# Mainboard.net
KiCad netlist of a schematic drawn in Altium Designer
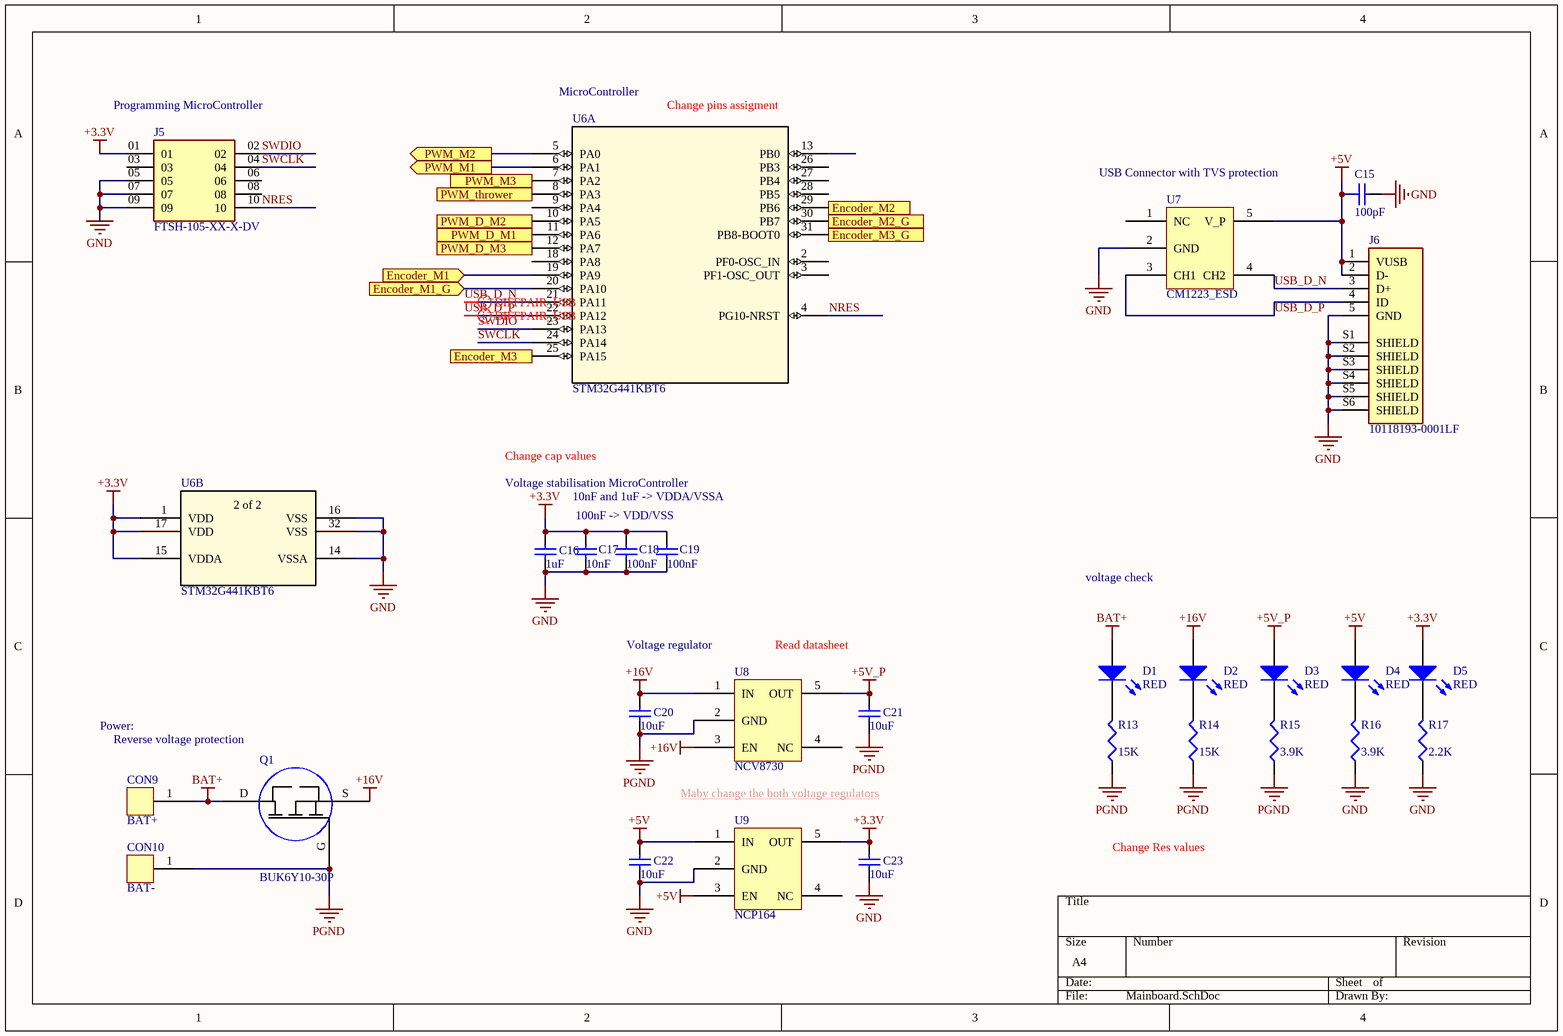
[diagram p0: Mainboard.SchDoc]

(export (version "E")
  (design (tool "Eeschema 10.0.6"))
  (components
    (comp (ref "C15")
      (value "100pF")
      (footprint "1608[0603]")
      (description "Capacitor (Semiconductor SIM Model)")
      (fields (field (name "Comment") "Cap Semi") (field (name "PUBLISHER") "Altium Limited"))
      (libsource (lib "Miscellaneous Devices") (part "Cap Semi"))
    )
    (comp (ref "C16")
      (value "1uF")
      (footprint "1608[0603]")
      (description "Capacitor (Semiconductor SIM Model)")
      (fields (field (name "Comment") "Cap Semi") (field (name "PUBLISHER") "Altium Limited"))
      (libsource (lib "Miscellaneous Devices") (part "Cap Semi"))
    )
    (comp (ref "C17")
      (value "10nF")
      (footprint "1608[0603]")
      (description "Capacitor (Semiconductor SIM Model)")
      (fields (field (name "Comment") "Cap Semi") (field (name "PUBLISHER") "Altium Limited"))
      (libsource (lib "Miscellaneous Devices") (part "Cap Semi"))
    )
    (comp (ref "C18")
      (value "100nF")
      (footprint "1608[0603]")
      (description "Capacitor (Semiconductor SIM Model)")
      (fields (field (name "Comment") "Cap Semi") (field (name "PUBLISHER") "Altium Limited"))
      (libsource (lib "Miscellaneous Devices") (part "Cap Semi"))
    )
    (comp (ref "C19")
      (value "100nF")
      (footprint "1608[0603]")
      (description "Capacitor (Semiconductor SIM Model)")
      (fields (field (name "Comment") "Cap Semi") (field (name "PUBLISHER") "Altium Limited"))
      (libsource (lib "Miscellaneous Devices") (part "Cap Semi"))
    )
    (comp (ref "C20")
      (value "10uF")
      (footprint "C1210")
      (description "Capacitor (Semiconductor SIM Model)")
      (fields (field (name "Comment") "Cap Semi") (field (name "PUBLISHER") "Altium Limited"))
      (libsource (lib "Miscellaneous Devices") (part "Cap Semi"))
    )
    (comp (ref "C21")
      (value "10uF")
      (footprint "C1210")
      (description "Capacitor (Semiconductor SIM Model)")
      (fields (field (name "Comment") "Cap Semi") (field (name "PUBLISHER") "Altium Limited"))
      (libsource (lib "Miscellaneous Devices") (part "Cap Semi"))
    )
    (comp (ref "C22")
      (value "10uF")
      (footprint "C1210")
      (description "Capacitor (Semiconductor SIM Model)")
      (fields (field (name "Comment") "Cap Semi") (field (name "PUBLISHER") "Altium Limited"))
      (libsource (lib "Miscellaneous Devices") (part "Cap Semi"))
    )
    (comp (ref "C23")
      (value "10uF")
      (footprint "C1210")
      (description "Capacitor (Semiconductor SIM Model)")
      (fields (field (name "Comment") "Cap Semi") (field (name "PUBLISHER") "Altium Limited"))
      (libsource (lib "Miscellaneous Devices") (part "Cap Semi"))
    )
    (comp (ref "CON9")
      (value "BAT+")
      (footprint "con_soldering")
      (libsource (lib "con_soldering") (part "Con_soldering"))
    )
    (comp (ref "CON10")
      (value "BAT-")
      (footprint "con_soldering")
      (libsource (lib "con_soldering") (part "Con_soldering"))
    )
    (comp (ref "D1")
      (value "RED")
      (footprint "3.2X1.6X1.1")
      (description "Typical RED, GREEN, YELLOW, AMBER GaAs LED")
      (fields (field (name "PUBLISHER") "Altium Limited"))
      (libsource (lib "Miscellaneous Devices") (part "LED2"))
    )
    (comp (ref "D2")
      (value "RED")
      (footprint "3.2X1.6X1.1")
      (description "Typical RED, GREEN, YELLOW, AMBER GaAs LED")
      (fields (field (name "PUBLISHER") "Altium Limited"))
      (libsource (lib "Miscellaneous Devices") (part "LED2"))
    )
    (comp (ref "D3")
      (value "RED")
      (footprint "3.2X1.6X1.1")
      (description "Typical RED, GREEN, YELLOW, AMBER GaAs LED")
      (fields (field (name "PUBLISHER") "Altium Limited"))
      (libsource (lib "Miscellaneous Devices") (part "LED2"))
    )
    (comp (ref "D4")
      (value "RED")
      (footprint "3.2X1.6X1.1")
      (description "Typical RED, GREEN, YELLOW, AMBER GaAs LED")
      (fields (field (name "PUBLISHER") "Altium Limited"))
      (libsource (lib "Miscellaneous Devices") (part "LED2"))
    )
    (comp (ref "D5")
      (value "RED")
      (footprint "3.2X1.6X1.1")
      (description "Typical RED, GREEN, YELLOW, AMBER GaAs LED")
      (fields (field (name "PUBLISHER") "Altium Limited"))
      (libsource (lib "Miscellaneous Devices") (part "LED2"))
    )
    (comp (ref "J5")
      (value "FTSH-105-XX-X-DV")
      (footprint "SAMTEC_FTSH-105-XX-X-DV:SAMTEC_FTSH-105-XX-X-DV")
      (description "Connector Header Surface Mount 10 position 0.050\" (1.27mm)")
      (libsource (lib "FTSH-105-XX-X-DV") (part "FTSH-105-XX-X-DV"))
    )
    (comp (ref "J6")
      (value "10118193-0001LF")
      (footprint "FCI_10118193-0001LF")
      (description "USB - micro B USB 2.0 Receptacle Connector 5 Position Surface Mount, Right Angle; Through Hole")
      (fields (field (name "MF") "Amphenol ICC"))
      (libsource (lib "SnapEDAsch") (part "10118193-0001LF"))
    )
    (comp (ref "Q1")
      (value "BUK6Y10-30P")
      (footprint "TRANS_PSMN5R5-60YS,115")
      (libsource (lib "BUK6Y10-30P") (part "BUK6Y10-30P"))
    )
    (comp (ref "R13")
      (value "15K")
      (footprint "J1-0603")
      (description "Resistor")
      (fields (field (name "Comment") "Res3") (field (name "PUBLISHER") "Altium Limited"))
      (libsource (lib "Miscellaneous Devices") (part "Res3"))
    )
    (comp (ref "R14")
      (value "15K")
      (footprint "J1-0603")
      (description "Resistor")
      (fields (field (name "Comment") "Res3") (field (name "PUBLISHER") "Altium Limited"))
      (libsource (lib "Miscellaneous Devices") (part "Res3"))
    )
    (comp (ref "R15")
      (value "3.9K")
      (footprint "J1-0603")
      (description "Resistor")
      (fields (field (name "Comment") "Res3") (field (name "PUBLISHER") "Altium Limited"))
      (libsource (lib "Miscellaneous Devices") (part "Res3"))
    )
    (comp (ref "R16")
      (value "3.9K")
      (footprint "J1-0603")
      (description "Resistor")
      (fields (field (name "Comment") "Res3") (field (name "PUBLISHER") "Altium Limited"))
      (libsource (lib "Miscellaneous Devices") (part "Res3"))
    )
    (comp (ref "R17")
      (value "2.2K")
      (footprint "J1-0603")
      (description "Resistor")
      (fields (field (name "Comment") "Res3") (field (name "PUBLISHER") "Altium Limited"))
      (libsource (lib "Miscellaneous Devices") (part "Res3"))
    )
    (comp (ref "U6")
      (value "STM32G441KBT6")
      (footprint "LQFP-32")
      (description "No Description Available")
      (fields (field (name "COPYRIGHT") "Copyright (C) 2021 Ultra Librarian. All rights reserved."))
      (libsource (lib "STM32G441KBT6") (part "STM32G441KBT6"))
    )
    (comp (ref "U7")
      (value "CM1223_ESD")
      (footprint "CM1223_ESD")
      (libsource (lib "CM1223_ESD") (part "CM1223_ESD"))
    )
    (comp (ref "U8")
      (value "NCV8730")
      (footprint "NCP164CSN330T1G_Voltage_regulator")
      (libsource (lib "NCV8730") (part "NCV8730"))
    )
    (comp (ref "U9")
      (value "NCP164")
      (footprint "NCP164CSN330T1G_Voltage_regulator")
      (libsource (lib "NCP164_voltage_5to3V3") (part "NCP164"))
    )
  )
  (nets
    (net (code "1") (name "+3.3V") (class "Default")
      (node (ref "C16") (pin "2") (pinfunction "2_2") (pintype "passive"))
      (node (ref "C17") (pin "2") (pinfunction "2_2") (pintype "passive"))
      (node (ref "C18") (pin "2") (pinfunction "2_2") (pintype "passive"))
      (node (ref "C19") (pin "2") (pinfunction "2_2") (pintype "passive"))
      (node (ref "C23") (pin "2") (pinfunction "2_2") (pintype "passive"))
      (node (ref "D5") (pin "1") (pinfunction "A_1") (pintype "passive"))
      (node (ref "J5") (pin "01") (pinfunction "01_01") (pintype "passive"))
      (node (ref "U6") (pin "1") (pinfunction "VDD_1") (pintype "power_in"))
      (node (ref "U6") (pin "15") (pinfunction "VDDA_15") (pintype "power_in"))
      (node (ref "U6") (pin "17") (pinfunction "VDD_17") (pintype "power_in"))
      (node (ref "U9") (pin "5") (pinfunction "OUT_5") (pintype "passive"))
    )
    (net (code "2") (name "+5V") (class "Default")
      (node (ref "C15") (pin "2") (pinfunction "2_2") (pintype "passive"))
      (node (ref "C22") (pin "2") (pinfunction "2_2") (pintype "passive"))
      (node (ref "D4") (pin "1") (pinfunction "A_1") (pintype "passive"))
      (node (ref "J6") (pin "1") (pinfunction "VUSB_1") (pintype "passive"))
      (node (ref "J6") (pin "2") (pinfunction "D-_2") (pintype "passive"))
      (node (ref "U7") (pin "5") (pinfunction "V_P_5") (pintype "passive"))
      (node (ref "U9") (pin "1") (pinfunction "IN_1") (pintype "passive"))
      (node (ref "U9") (pin "3") (pinfunction "EN_3") (pintype "passive"))
    )
    (net (code "3") (name "+5V_P") (class "Default")
      (node (ref "C21") (pin "2") (pinfunction "2_2") (pintype "passive"))
      (node (ref "D3") (pin "1") (pinfunction "A_1") (pintype "passive"))
      (node (ref "U8") (pin "5") (pinfunction "OUT_5") (pintype "passive"))
    )
    (net (code "4") (name "+16V") (class "Default")
      (node (ref "C20") (pin "2") (pinfunction "2_2") (pintype "passive"))
      (node (ref "D2") (pin "1") (pinfunction "A_1") (pintype "passive"))
      (node (ref "Q1") (pin "S") (pinfunction "S_S") (pintype "passive"))
      (node (ref "U8") (pin "1") (pinfunction "IN_1") (pintype "passive"))
      (node (ref "U8") (pin "3") (pinfunction "EN_3") (pintype "passive"))
    )
    (net (code "5") (name "/Encoder_M1") (class "Default")
      (node (ref "U6") (pin "19") (pinfunction "PA9_19") (pintype "bidirectional"))
    )
    (net (code "6") (name "/Encoder_M1_G") (class "Default")
      (node (ref "U6") (pin "20") (pinfunction "PA10_20") (pintype "bidirectional"))
    )
    (net (code "7") (name "/Encoder_M2") (class "Default")
      (node (ref "U6") (pin "29") (pinfunction "PB6_29") (pintype "bidirectional"))
    )
    (net (code "8") (name "/Encoder_M2_G") (class "Default")
      (node (ref "U6") (pin "30") (pinfunction "PB7_30") (pintype "bidirectional"))
    )
    (net (code "9") (name "/Encoder_M3") (class "Default")
      (node (ref "U6") (pin "25") (pinfunction "PA15_25") (pintype "bidirectional"))
    )
    (net (code "10") (name "/Encoder_M3_G") (class "Default")
      (node (ref "U6") (pin "31") (pinfunction "PB8-BOOT0_31") (pintype "bidirectional"))
    )
    (net (code "11") (name "/NRES") (class "Default")
      (node (ref "J5") (pin "10") (pinfunction "10_10") (pintype "passive"))
      (node (ref "U6") (pin "4") (pinfunction "PG10-NRST_4") (pintype "bidirectional"))
    )
    (net (code "12") (name "/PWM_D_M1") (class "Default")
      (node (ref "U6") (pin "11") (pinfunction "PA6_11") (pintype "bidirectional"))
    )
    (net (code "13") (name "/PWM_D_M2") (class "Default")
      (node (ref "U6") (pin "10") (pinfunction "PA5_10") (pintype "bidirectional"))
    )
    (net (code "14") (name "/PWM_D_M3") (class "Default")
      (node (ref "U6") (pin "12") (pinfunction "PA7_12") (pintype "bidirectional"))
    )
    (net (code "15") (name "/PWM_M1") (class "Default")
      (node (ref "U6") (pin "6") (pinfunction "PA1_6") (pintype "bidirectional"))
    )
    (net (code "16") (name "/PWM_M2") (class "Default")
      (node (ref "U6") (pin "5") (pinfunction "PA0_5") (pintype "bidirectional"))
    )
    (net (code "17") (name "/PWM_M3") (class "Default")
      (node (ref "U6") (pin "7") (pinfunction "PA2_7") (pintype "bidirectional"))
    )
    (net (code "18") (name "/PWM_thrower") (class "Default")
      (node (ref "U6") (pin "8") (pinfunction "PA3_8") (pintype "bidirectional"))
    )
    (net (code "19") (name "/SWCLK") (class "Default")
      (node (ref "J5") (pin "04") (pinfunction "04_04") (pintype "passive"))
      (node (ref "U6") (pin "24") (pinfunction "PA14_24") (pintype "bidirectional"))
    )
    (net (code "20") (name "/SWDIO") (class "Default")
      (node (ref "J5") (pin "02") (pinfunction "02_02") (pintype "passive"))
      (node (ref "U6") (pin "23") (pinfunction "PA13_23") (pintype "bidirectional"))
    )
    (net (code "21") (name "/USB_D_N") (class "Default")
      (node (ref "J6") (pin "3") (pinfunction "D+_3") (pintype "passive"))
      (node (ref "U6") (pin "21") (pinfunction "PA11_21") (pintype "bidirectional"))
      (node (ref "U7") (pin "4") (pinfunction "CH2_4") (pintype "passive"))
    )
    (net (code "22") (name "/USB_D_P") (class "Default")
      (node (ref "J6") (pin "4") (pinfunction "ID_4") (pintype "passive"))
      (node (ref "U6") (pin "22") (pinfunction "PA12_22") (pintype "bidirectional"))
      (node (ref "U7") (pin "3") (pinfunction "CH1_3") (pintype "passive"))
    )
    (net (code "23") (name "BAT+") (class "Default")
      (node (ref "CON9") (pin "1") (pintype "passive"))
      (node (ref "D1") (pin "1") (pinfunction "A_1") (pintype "passive"))
      (node (ref "Q1") (pin "D") (pinfunction "D_D") (pintype "passive"))
    )
    (net (code "24") (name "GND") (class "Default")
      (node (ref "C15") (pin "1") (pinfunction "1_1") (pintype "passive"))
      (node (ref "C16") (pin "1") (pinfunction "1_1") (pintype "passive"))
      (node (ref "C17") (pin "1") (pinfunction "1_1") (pintype "passive"))
      (node (ref "C18") (pin "1") (pinfunction "1_1") (pintype "passive"))
      (node (ref "C19") (pin "1") (pinfunction "1_1") (pintype "passive"))
      (node (ref "C22") (pin "1") (pinfunction "1_1") (pintype "passive"))
      (node (ref "C23") (pin "1") (pinfunction "1_1") (pintype "passive"))
      (node (ref "J5") (pin "05") (pinfunction "05_05") (pintype "passive"))
      (node (ref "J5") (pin "07") (pinfunction "07_07") (pintype "passive"))
      (node (ref "J5") (pin "09") (pinfunction "09_09") (pintype "passive"))
      (node (ref "J6") (pin "5") (pinfunction "GND_5") (pintype "passive"))
      (node (ref "J6") (pin "S1") (pinfunction "SHIELD_S1") (pintype "passive"))
      (node (ref "J6") (pin "S2") (pinfunction "SHIELD_S2") (pintype "passive"))
      (node (ref "J6") (pin "S3") (pinfunction "SHIELD_S3") (pintype "passive"))
      (node (ref "J6") (pin "S4") (pinfunction "SHIELD_S4") (pintype "passive"))
      (node (ref "J6") (pin "S5") (pinfunction "SHIELD_S5") (pintype "passive"))
      (node (ref "J6") (pin "S6") (pinfunction "SHIELD_S6") (pintype "passive"))
      (node (ref "R16") (pin "1") (pinfunction "1_1") (pintype "passive"))
      (node (ref "R17") (pin "1") (pinfunction "1_1") (pintype "passive"))
      (node (ref "U6") (pin "14") (pinfunction "VSSA_14") (pintype "power_in"))
      (node (ref "U6") (pin "16") (pinfunction "VSS_16") (pintype "power_in"))
      (node (ref "U6") (pin "32") (pinfunction "VSS_32") (pintype "power_in"))
      (node (ref "U7") (pin "2") (pinfunction "GND_2") (pintype "passive"))
      (node (ref "U9") (pin "2") (pinfunction "GND_2") (pintype "passive"))
    )
    (net (code "25") (name "Net-(D1-K)") (class "Default")
      (node (ref "D1") (pin "2") (pinfunction "K_2") (pintype "passive"))
      (node (ref "R13") (pin "2") (pinfunction "2_2") (pintype "passive"))
    )
    (net (code "26") (name "Net-(D2-K)") (class "Default")
      (node (ref "D2") (pin "2") (pinfunction "K_2") (pintype "passive"))
      (node (ref "R14") (pin "2") (pinfunction "2_2") (pintype "passive"))
    )
    (net (code "27") (name "Net-(D3-K)") (class "Default")
      (node (ref "D3") (pin "2") (pinfunction "K_2") (pintype "passive"))
      (node (ref "R15") (pin "2") (pinfunction "2_2") (pintype "passive"))
    )
    (net (code "28") (name "Net-(D4-K)") (class "Default")
      (node (ref "D4") (pin "2") (pinfunction "K_2") (pintype "passive"))
      (node (ref "R16") (pin "2") (pinfunction "2_2") (pintype "passive"))
    )
    (net (code "29") (name "Net-(D5-K)") (class "Default")
      (node (ref "D5") (pin "2") (pinfunction "K_2") (pintype "passive"))
      (node (ref "R17") (pin "2") (pinfunction "2_2") (pintype "passive"))
    )
    (net (code "30") (name "PGND") (class "Default")
      (node (ref "C20") (pin "1") (pinfunction "1_1") (pintype "passive"))
      (node (ref "C21") (pin "1") (pinfunction "1_1") (pintype "passive"))
      (node (ref "CON10") (pin "1") (pintype "passive"))
      (node (ref "Q1") (pin "G") (pinfunction "G_G") (pintype "passive"))
      (node (ref "R13") (pin "1") (pinfunction "1_1") (pintype "passive"))
      (node (ref "R14") (pin "1") (pinfunction "1_1") (pintype "passive"))
      (node (ref "R15") (pin "1") (pinfunction "1_1") (pintype "passive"))
      (node (ref "U8") (pin "2") (pinfunction "GND_2") (pintype "passive"))
    )
    (net (code "31") (name "unconnected-(J5-Pad03)") (class "Default")
      (node (ref "J5") (pin "03") (pinfunction "03_03") (pintype "passive"))
    )
    (net (code "32") (name "unconnected-(J5-Pad06)") (class "Default")
      (node (ref "J5") (pin "06") (pinfunction "06_06") (pintype "passive"))
    )
    (net (code "33") (name "unconnected-(J5-Pad08)") (class "Default")
      (node (ref "J5") (pin "08") (pinfunction "08_08") (pintype "passive"))
    )
    (net (code "34") (name "unconnected-(U6A-PA4-Pad9)") (class "Default")
      (node (ref "U6") (pin "9") (pinfunction "PA4_9") (pintype "bidirectional"))
    )
    (net (code "35") (name "unconnected-(U6A-PA8-Pad18)") (class "Default")
      (node (ref "U6") (pin "18") (pinfunction "PA8_18") (pintype "bidirectional"))
    )
    (net (code "36") (name "unconnected-(U6A-PB0-Pad13)") (class "Default")
      (node (ref "U6") (pin "13") (pinfunction "PB0_13") (pintype "bidirectional"))
    )
    (net (code "37") (name "unconnected-(U6A-PB3-Pad26)") (class "Default")
      (node (ref "U6") (pin "26") (pinfunction "PB3_26") (pintype "bidirectional"))
    )
    (net (code "38") (name "unconnected-(U6A-PB4-Pad27)") (class "Default")
      (node (ref "U6") (pin "27") (pinfunction "PB4_27") (pintype "bidirectional"))
    )
    (net (code "39") (name "unconnected-(U6A-PB5-Pad28)") (class "Default")
      (node (ref "U6") (pin "28") (pinfunction "PB5_28") (pintype "bidirectional"))
    )
    (net (code "40") (name "unconnected-(U6A-PF0-OSC_IN-Pad2)") (class "Default")
      (node (ref "U6") (pin "2") (pinfunction "PF0-OSC_IN_2") (pintype "bidirectional"))
    )
    (net (code "41") (name "unconnected-(U6A-PF1-OSC_OUT-Pad3)") (class "Default")
      (node (ref "U6") (pin "3") (pinfunction "PF1-OSC_OUT_3") (pintype "bidirectional"))
    )
    (net (code "42") (name "unconnected-(U7-NC-Pad1)") (class "Default")
      (node (ref "U7") (pin "1") (pinfunction "NC_1") (pintype "passive"))
    )
    (net (code "43") (name "unconnected-(U8-NC-Pad4)") (class "Default")
      (node (ref "U8") (pin "4") (pinfunction "NC_4") (pintype "passive"))
    )
    (net (code "44") (name "unconnected-(U9-NC-Pad4)") (class "Default")
      (node (ref "U9") (pin "4") (pinfunction "NC_4") (pintype "passive"))
    )
  )
)
